# avrdroid.net
KiCad netlist of a schematic drawn in EAGLE
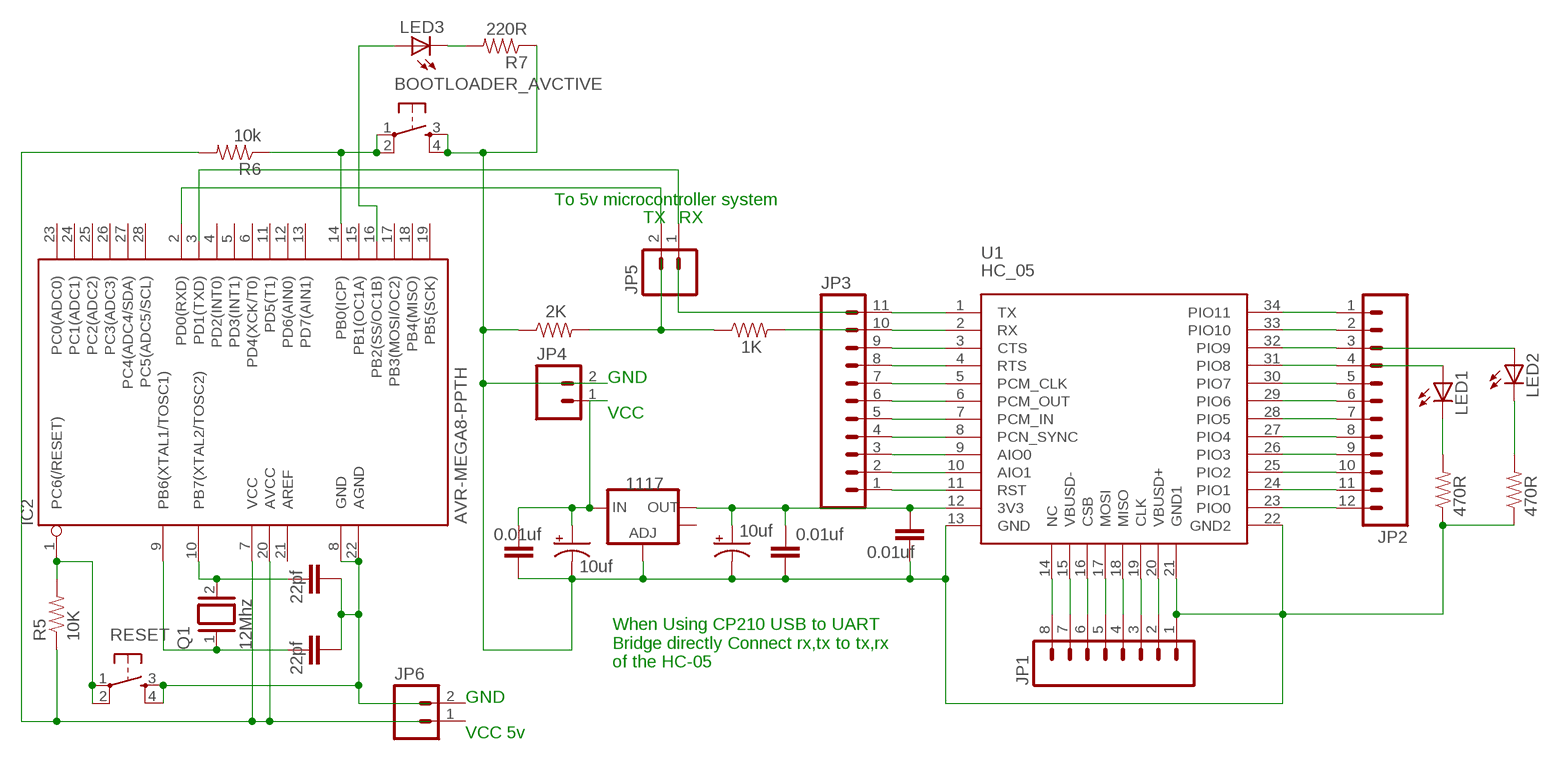
[diagram p0: schematic, sheet 1]

(export (version "E")
  (design (tool "Eeschema 10.0.6"))
  (components
    (comp (ref "BOOTLOADER_AVCTIVE")
      (value "TAC_SWITCH12MM")
      (footprint "eagle-import:TACTILE-PTH-12MM")
      (libsource (lib "eagle-import") (part "TAC_SWITCH12MM"))
    )
    (comp (ref "C1")
      (value "10uf")
      (footprint "eagle-import:EIA3216")
      (libsource (lib "eagle-import") (part "CAP_POL1206"))
    )
    (comp (ref "C2")
      (value "10uf")
      (footprint "eagle-import:EIA3216")
      (libsource (lib "eagle-import") (part "CAP_POL1206"))
    )
    (comp (ref "C3")
      (value "0.01uf")
      (footprint "eagle-import:CAP-PTH-SMALL")
      (libsource (lib "eagle-import") (part "CAPPTH"))
    )
    (comp (ref "C4")
      (value "0.01uf")
      (footprint "eagle-import:CAP-PTH-SMALL")
      (libsource (lib "eagle-import") (part "CAPPTH"))
    )
    (comp (ref "C5")
      (value "0.01uf")
      (footprint "eagle-import:CAP-PTH-SMALL")
      (libsource (lib "eagle-import") (part "CAPPTH"))
    )
    (comp (ref "C6")
      (value "22pf")
      (footprint "eagle-import:CAP-PTH-SMALL")
      (libsource (lib "eagle-import") (part "CAPPTH"))
    )
    (comp (ref "C7")
      (value "22pf")
      (footprint "eagle-import:CAP-PTH-SMALL")
      (libsource (lib "eagle-import") (part "CAPPTH"))
    )
    (comp (ref "IC1")
      (value "1117")
      (footprint "eagle-import:SOT223")
      (libsource (lib "eagle-import") (part "V_REG_LM1117SOT223"))
    )
    (comp (ref "IC2")
      (value "AVR-MEGA8-PPTH")
      (footprint "eagle-import:DIL28-3")
      (libsource (lib "eagle-import") (part "AVR-MEGA8-PPTH"))
    )
    (comp (ref "JP1")
      (value "M08")
      (footprint "eagle-import:1X08")
      (libsource (lib "eagle-import") (part "M08"))
    )
    (comp (ref "JP2")
      (value "M12PTH")
      (footprint "eagle-import:1X12")
      (libsource (lib "eagle-import") (part "M12PTH"))
    )
    (comp (ref "JP3")
      (value "M11PTH")
      (footprint "eagle-import:1X11")
      (libsource (lib "eagle-import") (part "M11PTH"))
    )
    (comp (ref "JP4")
      (value "M02PTH")
      (footprint "eagle-import:1X02")
      (libsource (lib "eagle-import") (part "M02PTH"))
    )
    (comp (ref "JP5")
      (value "M02")
      (footprint "eagle-import:1X02_LONGPADS")
      (libsource (lib "eagle-import") (part "M02"))
    )
    (comp (ref "JP6")
      (value "M02PTH")
      (footprint "eagle-import:1X02")
      (libsource (lib "eagle-import") (part "M02PTH"))
    )
    (comp (ref "LED1")
      (value "LED3MM")
      (footprint "eagle-import:LED3MM")
      (libsource (lib "eagle-import") (part "LED3MM"))
    )
    (comp (ref "LED2")
      (value "LED3MM")
      (footprint "eagle-import:LED3MM")
      (libsource (lib "eagle-import") (part "LED3MM"))
    )
    (comp (ref "LED3")
      (value "LED3MM")
      (footprint "eagle-import:LED3MM")
      (libsource (lib "eagle-import") (part "LED3MM"))
    )
    (comp (ref "Q1")
      (value "12Mhz")
      (footprint "eagle-import:QS")
      (libsource (lib "eagle-import") (part "XTAL/S"))
    )
    (comp (ref "R1")
      (value "1K")
      (footprint "eagle-import:AXIAL-0.3")
      (libsource (lib "eagle-import") (part "RESISTORPTH1"))
    )
    (comp (ref "R2")
      (value "2K")
      (footprint "eagle-import:AXIAL-0.3")
      (libsource (lib "eagle-import") (part "RESISTORPTH1"))
    )
    (comp (ref "R3")
      (value "470R")
      (footprint "eagle-import:AXIAL-0.3")
      (libsource (lib "eagle-import") (part "RESISTORPTH1"))
    )
    (comp (ref "R4")
      (value "470R")
      (footprint "eagle-import:AXIAL-0.3")
      (libsource (lib "eagle-import") (part "RESISTORPTH1"))
    )
    (comp (ref "R5")
      (value "10K")
      (footprint "eagle-import:AXIAL-0.3")
      (libsource (lib "eagle-import") (part "RESISTORPTH1"))
    )
    (comp (ref "R6")
      (value "10k")
      (footprint "eagle-import:AXIAL-0.3")
      (libsource (lib "eagle-import") (part "RESISTORPTH1"))
    )
    (comp (ref "R7")
      (value "220R")
      (footprint "eagle-import:AXIAL-0.3")
      (libsource (lib "eagle-import") (part "RESISTORPTH1"))
    )
    (comp (ref "RESET")
      (value "TAC_SWITCH12MM")
      (footprint "eagle-import:TACTILE-PTH-12MM")
      (libsource (lib "eagle-import") (part "TAC_SWITCH12MM"))
    )
    (comp (ref "U1")
      (value "HC_05")
      (footprint "eagle-import:BLUETOOTH_SMD")
      (libsource (lib "eagle-import") (part "HC_05"))
    )
  )
  (nets
    (net (code "1") (name "Net-(C1-+)") (class "Default")
      (node (ref "C1") (pin "A") (pinfunction "+_A") (pintype "passive"))
      (node (ref "C4") (pin "1") (pinfunction "1_1") (pintype "passive"))
      (node (ref "IC1") (pin "3") (pinfunction "IN_3") (pintype "input"))
      (node (ref "JP4") (pin "1") (pinfunction "1_1") (pintype "passive"))
    )
    (net (code "2") (name "Net-(C1--)") (class "Default")
      (node (ref "BOOTLOADER_AVCTIVE") (pin "3") (pinfunction "3_3") (pintype "passive"))
      (node (ref "BOOTLOADER_AVCTIVE") (pin "4") (pinfunction "4_4") (pintype "passive"))
      (node (ref "C1") (pin "C") (pinfunction "-_C") (pintype "passive"))
      (node (ref "C2") (pin "C") (pinfunction "-_C") (pintype "passive"))
      (node (ref "C3") (pin "2") (pinfunction "2_2") (pintype "passive"))
      (node (ref "C4") (pin "2") (pinfunction "2_2") (pintype "passive"))
      (node (ref "C5") (pin "2") (pinfunction "2_2") (pintype "passive"))
      (node (ref "IC1") (pin "1") (pinfunction "ADJ_1") (pintype "input"))
      (node (ref "JP1") (pin "1") (pinfunction "1_1") (pintype "passive"))
      (node (ref "JP4") (pin "2") (pinfunction "2_2") (pintype "passive"))
      (node (ref "R2") (pin "P$1") (pinfunction "1_P$1") (pintype "passive"))
      (node (ref "R3") (pin "P$1") (pinfunction "1_P$1") (pintype "passive"))
      (node (ref "R4") (pin "P$1") (pinfunction "1_P$1") (pintype "passive"))
      (node (ref "R7") (pin "P$1") (pinfunction "1_P$1") (pintype "passive"))
      (node (ref "U1") (pin "13") (pinfunction "GND_13") (pintype "bidirectional"))
      (node (ref "U1") (pin "21") (pinfunction "GND1_21") (pintype "bidirectional"))
      (node (ref "U1") (pin "22") (pinfunction "GND2_22") (pintype "bidirectional"))
    )
    (net (code "3") (name "Net-(C2-+)") (class "Default")
      (node (ref "C2") (pin "A") (pinfunction "+_A") (pintype "passive"))
      (node (ref "C3") (pin "1") (pinfunction "1_1") (pintype "passive"))
      (node (ref "C5") (pin "1") (pinfunction "1_1") (pintype "passive"))
      (node (ref "IC1") (pin "2") (pinfunction "OUT_2") (pintype "output"))
      (node (ref "U1") (pin "12") (pinfunction "3V3_12") (pintype "bidirectional"))
    )
    (net (code "4") (name "Net-(IC2-AGND)") (class "Default")
      (node (ref "C6") (pin "2") (pinfunction "2_2") (pintype "passive"))
      (node (ref "C7") (pin "2") (pinfunction "2_2") (pintype "passive"))
      (node (ref "IC2") (pin "22") (pinfunction "AGND_22") (pintype "bidirectional"))
      (node (ref "IC2") (pin "8") (pinfunction "GND_8") (pintype "bidirectional"))
      (node (ref "RESET") (pin "3") (pinfunction "3_3") (pintype "passive"))
      (node (ref "RESET") (pin "4") (pinfunction "4_4") (pintype "passive"))
    )
    (net (code "5") (name "Net-(IC2-AVCC)") (class "Default")
      (node (ref "IC2") (pin "20") (pinfunction "AVCC_20") (pintype "bidirectional"))
      (node (ref "IC2") (pin "7") (pinfunction "VCC_7") (pintype "bidirectional"))
      (node (ref "R5") (pin "P$1") (pinfunction "1_P$1") (pintype "passive"))
      (node (ref "R6") (pin "P$2") (pinfunction "2_P$2") (pintype "passive"))
    )
    (net (code "6") (name "Net-(IC2-PB0(ICP))") (class "Default")
      (node (ref "BOOTLOADER_AVCTIVE") (pin "1") (pinfunction "1_1") (pintype "passive"))
      (node (ref "BOOTLOADER_AVCTIVE") (pin "2") (pinfunction "2_2") (pintype "passive"))
      (node (ref "IC2") (pin "14") (pinfunction "PB0(ICP)_14") (pintype "bidirectional"))
      (node (ref "R6") (pin "P$1") (pinfunction "1_P$1") (pintype "passive"))
    )
    (net (code "7") (name "Net-(IC2-PB6(XTAL1{slash}TOSC1))") (class "Default")
      (node (ref "C6") (pin "1") (pinfunction "1_1") (pintype "passive"))
      (node (ref "IC2") (pin "9") (pinfunction "PB6(XTAL1/TOSC1)_9") (pintype "bidirectional"))
      (node (ref "Q1") (pin "1") (pinfunction "1_1") (pintype "passive"))
    )
    (net (code "8") (name "Net-(IC2-PB7(XTAL2{slash}TOSC2))") (class "Default")
      (node (ref "C7") (pin "1") (pinfunction "1_1") (pintype "passive"))
      (node (ref "IC2") (pin "10") (pinfunction "PB7(XTAL2/TOSC2)_10") (pintype "bidirectional"))
      (node (ref "Q1") (pin "2") (pinfunction "2_2") (pintype "passive"))
    )
    (net (code "9") (name "Net-(IC2-PC6({slash}RESET))") (class "Default")
      (node (ref "IC2") (pin "1") (pinfunction "PC6(/RESET)_1") (pintype "bidirectional"))
      (node (ref "R5") (pin "P$2") (pinfunction "2_P$2") (pintype "passive"))
      (node (ref "RESET") (pin "1") (pinfunction "1_1") (pintype "passive"))
      (node (ref "RESET") (pin "2") (pinfunction "2_2") (pintype "passive"))
    )
    (net (code "10") (name "Net-(IC2-PD0(RXD))") (class "Default")
      (node (ref "IC2") (pin "2") (pinfunction "PD0(RXD)_2") (pintype "bidirectional"))
      (node (ref "JP5") (pin "2") (pinfunction "2_2") (pintype "passive"))
    )
    (net (code "11") (name "Net-(LED1-C)") (class "Default")
      (node (ref "LED1") (pin "K") (pinfunction "C_K") (pintype "passive"))
      (node (ref "R3") (pin "P$2") (pinfunction "2_P$2") (pintype "passive"))
    )
    (net (code "12") (name "Net-(LED2-C)") (class "Default")
      (node (ref "LED2") (pin "K") (pinfunction "C_K") (pintype "passive"))
      (node (ref "R4") (pin "P$2") (pinfunction "2_P$2") (pintype "passive"))
    )
    (net (code "13") (name "Net-(LED3-C)") (class "Default")
      (node (ref "LED3") (pin "K") (pinfunction "C_K") (pintype "passive"))
      (node (ref "R7") (pin "P$2") (pinfunction "2_P$2") (pintype "passive"))
    )
    (net (code "14") (name "Net-(R1-1)") (class "Default")
      (node (ref "R1") (pin "P$1") (pinfunction "1_P$1") (pintype "passive"))
      (node (ref "R2") (pin "P$2") (pinfunction "2_P$2") (pintype "passive"))
    )
    (net (code "15") (name "Net-(U1-AIO0)") (class "Default")
      (node (ref "JP3") (pin "3") (pinfunction "3_3") (pintype "passive"))
      (node (ref "U1") (pin "9") (pinfunction "AIO0_9") (pintype "bidirectional"))
    )
    (net (code "16") (name "Net-(U1-AIO1)") (class "Default")
      (node (ref "JP3") (pin "2") (pinfunction "2_2") (pintype "passive"))
      (node (ref "U1") (pin "10") (pinfunction "AIO1_10") (pintype "bidirectional"))
    )
    (net (code "17") (name "Net-(U1-CLK)") (class "Default")
      (node (ref "JP1") (pin "3") (pinfunction "3_3") (pintype "passive"))
      (node (ref "U1") (pin "19") (pinfunction "CLK_19") (pintype "bidirectional"))
    )
    (net (code "18") (name "Net-(U1-CSB)") (class "Default")
      (node (ref "JP1") (pin "6") (pinfunction "6_6") (pintype "passive"))
      (node (ref "U1") (pin "16") (pinfunction "CSB_16") (pintype "bidirectional"))
    )
    (net (code "19") (name "Net-(U1-CTS)") (class "Default")
      (node (ref "JP3") (pin "9") (pinfunction "9_9") (pintype "passive"))
      (node (ref "U1") (pin "3") (pinfunction "CTS_3") (pintype "bidirectional"))
    )
    (net (code "20") (name "Net-(U1-MISO)") (class "Default")
      (node (ref "JP1") (pin "4") (pinfunction "4_4") (pintype "passive"))
      (node (ref "U1") (pin "18") (pinfunction "MISO_18") (pintype "bidirectional"))
    )
    (net (code "21") (name "Net-(U1-MOSI)") (class "Default")
      (node (ref "JP1") (pin "5") (pinfunction "5_5") (pintype "passive"))
      (node (ref "U1") (pin "17") (pinfunction "MOSI_17") (pintype "bidirectional"))
    )
    (net (code "22") (name "Net-(U1-NC)") (class "Default")
      (node (ref "JP1") (pin "8") (pinfunction "8_8") (pintype "passive"))
      (node (ref "U1") (pin "14") (pinfunction "NC_14") (pintype "bidirectional"))
    )
    (net (code "23") (name "Net-(U1-PCM_CLK)") (class "Default")
      (node (ref "JP3") (pin "7") (pinfunction "7_7") (pintype "passive"))
      (node (ref "U1") (pin "5") (pinfunction "PCM_CLK_5") (pintype "bidirectional"))
    )
    (net (code "24") (name "Net-(U1-PCM_IN)") (class "Default")
      (node (ref "JP3") (pin "5") (pinfunction "5_5") (pintype "passive"))
      (node (ref "U1") (pin "7") (pinfunction "PCM_IN_7") (pintype "bidirectional"))
    )
    (net (code "25") (name "Net-(U1-PCM_OUT)") (class "Default")
      (node (ref "JP3") (pin "6") (pinfunction "6_6") (pintype "passive"))
      (node (ref "U1") (pin "6") (pinfunction "PCM_OUT_6") (pintype "bidirectional"))
    )
    (net (code "26") (name "Net-(U1-PCN_SYNC)") (class "Default")
      (node (ref "JP3") (pin "4") (pinfunction "4_4") (pintype "passive"))
      (node (ref "U1") (pin "8") (pinfunction "PCN_SYNC_8") (pintype "bidirectional"))
    )
    (net (code "27") (name "Net-(U1-PIO0)") (class "Default")
      (node (ref "JP2") (pin "12") (pinfunction "12_12") (pintype "passive"))
      (node (ref "U1") (pin "23") (pinfunction "PIO0_23") (pintype "bidirectional"))
    )
    (net (code "28") (name "Net-(U1-PIO1)") (class "Default")
      (node (ref "JP2") (pin "11") (pinfunction "11_11") (pintype "passive"))
      (node (ref "U1") (pin "24") (pinfunction "PIO1_24") (pintype "bidirectional"))
    )
    (net (code "29") (name "Net-(U1-PIO2)") (class "Default")
      (node (ref "JP2") (pin "10") (pinfunction "10_10") (pintype "passive"))
      (node (ref "U1") (pin "25") (pinfunction "PIO2_25") (pintype "bidirectional"))
    )
    (net (code "30") (name "Net-(U1-PIO3)") (class "Default")
      (node (ref "JP2") (pin "9") (pinfunction "9_9") (pintype "passive"))
      (node (ref "U1") (pin "26") (pinfunction "PIO3_26") (pintype "bidirectional"))
    )
    (net (code "31") (name "Net-(U1-PIO4)") (class "Default")
      (node (ref "JP2") (pin "8") (pinfunction "8_8") (pintype "passive"))
      (node (ref "U1") (pin "27") (pinfunction "PIO4_27") (pintype "bidirectional"))
    )
    (net (code "32") (name "Net-(U1-PIO5)") (class "Default")
      (node (ref "JP2") (pin "7") (pinfunction "7_7") (pintype "passive"))
      (node (ref "U1") (pin "28") (pinfunction "PIO5_28") (pintype "bidirectional"))
    )
    (net (code "33") (name "Net-(U1-PIO6)") (class "Default")
      (node (ref "JP2") (pin "6") (pinfunction "6_6") (pintype "passive"))
      (node (ref "U1") (pin "29") (pinfunction "PIO6_29") (pintype "bidirectional"))
    )
    (net (code "34") (name "Net-(U1-PIO7)") (class "Default")
      (node (ref "JP2") (pin "5") (pinfunction "5_5") (pintype "passive"))
      (node (ref "U1") (pin "30") (pinfunction "PIO7_30") (pintype "bidirectional"))
    )
    (net (code "35") (name "Net-(U1-PIO8)") (class "Default")
      (node (ref "JP2") (pin "4") (pinfunction "4_4") (pintype "passive"))
      (node (ref "U1") (pin "31") (pinfunction "PIO8_31") (pintype "bidirectional"))
    )
    (net (code "36") (name "Net-(U1-PIO9)") (class "Default")
      (node (ref "JP2") (pin "3") (pinfunction "3_3") (pintype "passive"))
      (node (ref "U1") (pin "32") (pinfunction "PIO9_32") (pintype "bidirectional"))
    )
    (net (code "37") (name "Net-(U1-PIO10)") (class "Default")
      (node (ref "JP2") (pin "2") (pinfunction "2_2") (pintype "passive"))
      (node (ref "U1") (pin "33") (pinfunction "PIO10_33") (pintype "bidirectional"))
    )
    (net (code "38") (name "Net-(U1-PIO11)") (class "Default")
      (node (ref "JP2") (pin "1") (pinfunction "1_1") (pintype "passive"))
      (node (ref "U1") (pin "34") (pinfunction "PIO11_34") (pintype "bidirectional"))
    )
    (net (code "39") (name "Net-(U1-RST)") (class "Default")
      (node (ref "JP3") (pin "1") (pinfunction "1_1") (pintype "passive"))
      (node (ref "U1") (pin "11") (pinfunction "RST_11") (pintype "bidirectional"))
    )
    (net (code "40") (name "Net-(U1-RTS)") (class "Default")
      (node (ref "JP3") (pin "8") (pinfunction "8_8") (pintype "passive"))
      (node (ref "U1") (pin "4") (pinfunction "RTS_4") (pintype "bidirectional"))
    )
    (net (code "41") (name "Net-(U1-RX)") (class "Default")
      (node (ref "JP3") (pin "10") (pinfunction "10_10") (pintype "passive"))
      (node (ref "U1") (pin "2") (pinfunction "RX_2") (pintype "bidirectional"))
    )
    (net (code "42") (name "Net-(U1-TX)") (class "Default")
      (node (ref "JP3") (pin "11") (pinfunction "11_11") (pintype "passive"))
      (node (ref "U1") (pin "1") (pinfunction "TX_1") (pintype "bidirectional"))
    )
    (net (code "43") (name "Net-(U1-VBUSD+)") (class "Default")
      (node (ref "JP1") (pin "2") (pinfunction "2_2") (pintype "passive"))
      (node (ref "U1") (pin "20") (pinfunction "VBUSD+_20") (pintype "bidirectional"))
    )
    (net (code "44") (name "Net-(U1-VBUSD-)") (class "Default")
      (node (ref "JP1") (pin "7") (pinfunction "7_7") (pintype "passive"))
      (node (ref "U1") (pin "15") (pinfunction "VBUSD-_15") (pintype "bidirectional"))
    )
    (net (code "45") (name "unconnected-(IC1-OUT-Pad4)") (class "Default")
      (node (ref "IC1") (pin "4") (pinfunction "OUT_4") (pintype "output"))
    )
    (net (code "46") (name "unconnected-(IC2-AREF-Pad21)") (class "Default")
      (node (ref "IC2") (pin "21") (pinfunction "AREF_21") (pintype "bidirectional"))
    )
    (net (code "47") (name "unconnected-(IC2-PB1(OC1A)-Pad15)") (class "Default")
      (node (ref "IC2") (pin "15") (pinfunction "PB1(OC1A)_15") (pintype "bidirectional"))
    )
    (net (code "48") (name "unconnected-(IC2-PB2(SS{slash}OC1B)-Pad16)") (class "Default")
      (node (ref "IC2") (pin "16") (pinfunction "PB2(SS/OC1B)_16") (pintype "bidirectional"))
    )
    (net (code "49") (name "unconnected-(IC2-PB3(MOSI{slash}OC2)-Pad17)") (class "Default")
      (node (ref "IC2") (pin "17") (pinfunction "PB3(MOSI/OC2)_17") (pintype "bidirectional"))
    )
    (net (code "50") (name "unconnected-(IC2-PB4(MISO)-Pad18)") (class "Default")
      (node (ref "IC2") (pin "18") (pinfunction "PB4(MISO)_18") (pintype "bidirectional"))
    )
    (net (code "51") (name "unconnected-(IC2-PB5(SCK)-Pad19)") (class "Default")
      (node (ref "IC2") (pin "19") (pinfunction "PB5(SCK)_19") (pintype "bidirectional"))
    )
    (net (code "52") (name "unconnected-(IC2-PC0(ADC0)-Pad23)") (class "Default")
      (node (ref "IC2") (pin "23") (pinfunction "PC0(ADC0)_23") (pintype "bidirectional"))
    )
    (net (code "53") (name "unconnected-(IC2-PC1(ADC1)-Pad24)") (class "Default")
      (node (ref "IC2") (pin "24") (pinfunction "PC1(ADC1)_24") (pintype "bidirectional"))
    )
    (net (code "54") (name "unconnected-(IC2-PC2(ADC2)-Pad25)") (class "Default")
      (node (ref "IC2") (pin "25") (pinfunction "PC2(ADC2)_25") (pintype "bidirectional"))
    )
    (net (code "55") (name "unconnected-(IC2-PC3(ADC3)-Pad26)") (class "Default")
      (node (ref "IC2") (pin "26") (pinfunction "PC3(ADC3)_26") (pintype "bidirectional"))
    )
    (net (code "56") (name "unconnected-(IC2-PC4(ADC4{slash}SDA)-Pad27)") (class "Default")
      (node (ref "IC2") (pin "27") (pinfunction "PC4(ADC4/SDA)_27") (pintype "bidirectional"))
    )
    (net (code "57") (name "unconnected-(IC2-PC5(ADC5{slash}SCL)-Pad28)") (class "Default")
      (node (ref "IC2") (pin "28") (pinfunction "PC5(ADC5/SCL)_28") (pintype "bidirectional"))
    )
    (net (code "58") (name "unconnected-(IC2-PD1(TXD)-Pad3)") (class "Default")
      (node (ref "IC2") (pin "3") (pinfunction "PD1(TXD)_3") (pintype "bidirectional"))
    )
    (net (code "59") (name "unconnected-(IC2-PD2(INT0)-Pad4)") (class "Default")
      (node (ref "IC2") (pin "4") (pinfunction "PD2(INT0)_4") (pintype "bidirectional"))
    )
    (net (code "60") (name "unconnected-(IC2-PD3(INT1)-Pad5)") (class "Default")
      (node (ref "IC2") (pin "5") (pinfunction "PD3(INT1)_5") (pintype "bidirectional"))
    )
    (net (code "61") (name "unconnected-(IC2-PD4(XCK{slash}T0)-Pad6)") (class "Default")
      (node (ref "IC2") (pin "6") (pinfunction "PD4(XCK/T0)_6") (pintype "bidirectional"))
    )
    (net (code "62") (name "unconnected-(IC2-PD5(T1)-Pad11)") (class "Default")
      (node (ref "IC2") (pin "11") (pinfunction "PD5(T1)_11") (pintype "bidirectional"))
    )
    (net (code "63") (name "unconnected-(IC2-PD6(AIN0)-Pad12)") (class "Default")
      (node (ref "IC2") (pin "12") (pinfunction "PD6(AIN0)_12") (pintype "bidirectional"))
    )
    (net (code "64") (name "unconnected-(IC2-PD7(AIN1)-Pad13)") (class "Default")
      (node (ref "IC2") (pin "13") (pinfunction "PD7(AIN1)_13") (pintype "bidirectional"))
    )
    (net (code "65") (name "unconnected-(JP5-Pad1)") (class "Default")
      (node (ref "JP5") (pin "1") (pinfunction "1_1") (pintype "passive"))
    )
    (net (code "66") (name "unconnected-(JP6-Pad1)") (class "Default")
      (node (ref "JP6") (pin "1") (pinfunction "1_1") (pintype "passive"))
    )
    (net (code "67") (name "unconnected-(JP6-Pad2)") (class "Default")
      (node (ref "JP6") (pin "2") (pinfunction "2_2") (pintype "passive"))
    )
    (net (code "68") (name "unconnected-(LED1-PadA)") (class "Default")
      (node (ref "LED1") (pin "A") (pinfunction "A_A") (pintype "passive"))
    )
    (net (code "69") (name "unconnected-(LED2-PadA)") (class "Default")
      (node (ref "LED2") (pin "A") (pinfunction "A_A") (pintype "passive"))
    )
    (net (code "70") (name "unconnected-(LED3-PadA)") (class "Default")
      (node (ref "LED3") (pin "A") (pinfunction "A_A") (pintype "passive"))
    )
    (net (code "71") (name "unconnected-(R1-2-PadP$2)") (class "Default")
      (node (ref "R1") (pin "P$2") (pinfunction "2_P$2") (pintype "passive"))
    )
  )
)
